# I2C_Expander.net
KiCad netlist of a schematic drawn in Altium Designer
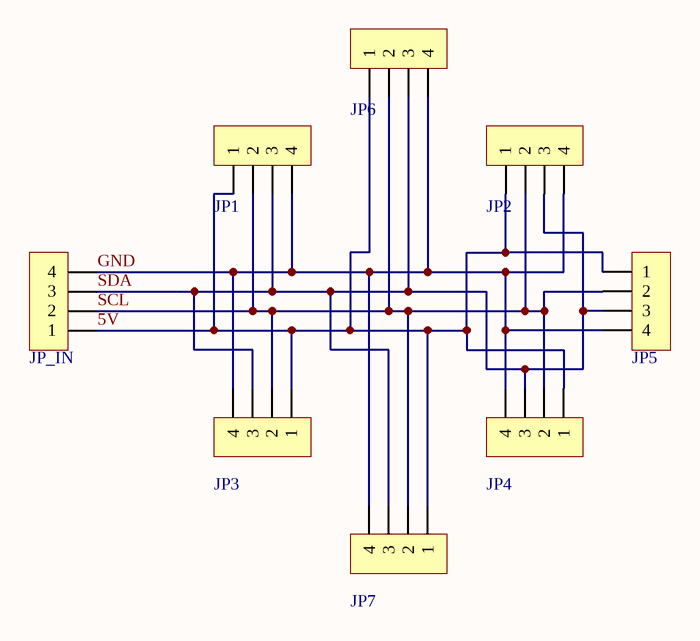
[diagram p0: I2C_Expander.SchDoc]

(export (version "E")
  (design (tool "Eeschema 10.0.6"))
  (components
    (comp (ref "JP1")
      (value "HDR-1X4")
      (footprint "MX 1.25-WS-4P")
      (description "4P接插件")
      (fields (field (name "版权归属") "源创客"))
      (libsource (lib "") (part "Header 4_1"))
    )
    (comp (ref "JP2")
      (value "HDR-1X4")
      (footprint "MX 1.25-WS-4P")
      (description "4P接插件")
      (fields (field (name "版权归属") "源创客"))
      (libsource (lib "") (part "Header 4_1"))
    )
    (comp (ref "JP3")
      (value "HDR-1X4")
      (footprint "MX 1.25-WS-4P")
      (description "4P接插件")
      (fields (field (name "版权归属") "源创客"))
      (libsource (lib "4.2   - 接插件-脚距1.25") (part "Header 4"))
    )
    (comp (ref "JP4")
      (value "HDR-1X4")
      (footprint "MX 1.25-WS-4P")
      (description "4P接插件")
      (fields (field (name "版权归属") "源创客"))
      (libsource (lib "4.2   - 接插件-脚距1.25") (part "Header 4"))
    )
    (comp (ref "JP5")
      (value "HDR-1X4")
      (footprint "HDR2.54-LI-4P")
      (description "4P接插件")
      (fields (field (name "版权归属") "源创客"))
      (libsource (lib "") (part "Header 4_1"))
    )
    (comp (ref "JP6")
      (value "HDR-1X4")
      (footprint "HDR2.54-LI-4P")
      (description "4P接插件")
      (fields (field (name "版权归属") "源创客"))
      (libsource (lib "4.5   - 接插件-脚距2.54") (part "Header 4"))
    )
    (comp (ref "JP7")
      (value "HDR-1X4")
      (footprint "HDR2.54-LI-4P")
      (description "4P接插件")
      (fields (field (name "版权归属") "源创客"))
      (libsource (lib "") (part "Header 4_2"))
    )
    (comp (ref "JP_IN")
      (value "HDR-1X4")
      (footprint "MX 1.25-WS-4P")
      (description "4P接插件")
      (fields (field (name "版权归属") "源创客"))
      (libsource (lib "") (part "Header 4_2"))
    )
  )
  (nets
    (net (code "1") (name "/5V") (class "Default")
      (node (ref "JP1") (pin "1") (pinfunction "1_1") (pintype "passive"))
      (node (ref "JP2") (pin "1") (pinfunction "1_1") (pintype "passive"))
      (node (ref "JP3") (pin "1") (pinfunction "1_1") (pintype "passive"))
      (node (ref "JP4") (pin "1") (pinfunction "1_1") (pintype "passive"))
      (node (ref "JP5") (pin "1") (pinfunction "1_1") (pintype "passive"))
      (node (ref "JP6") (pin "1") (pinfunction "1_1") (pintype "passive"))
      (node (ref "JP7") (pin "1") (pinfunction "1_1") (pintype "passive"))
      (node (ref "JP_IN") (pin "1") (pinfunction "1_1") (pintype "passive"))
    )
    (net (code "2") (name "/GND") (class "Default")
      (node (ref "JP1") (pin "4") (pinfunction "4_4") (pintype "passive"))
      (node (ref "JP2") (pin "4") (pinfunction "4_4") (pintype "passive"))
      (node (ref "JP3") (pin "4") (pinfunction "4_4") (pintype "passive"))
      (node (ref "JP4") (pin "4") (pinfunction "4_4") (pintype "passive"))
      (node (ref "JP5") (pin "4") (pinfunction "4_4") (pintype "passive"))
      (node (ref "JP6") (pin "4") (pinfunction "4_4") (pintype "passive"))
      (node (ref "JP7") (pin "4") (pinfunction "4_4") (pintype "passive"))
      (node (ref "JP_IN") (pin "4") (pinfunction "4_4") (pintype "passive"))
    )
    (net (code "3") (name "/SCL") (class "Default")
      (node (ref "JP1") (pin "2") (pinfunction "2_2") (pintype "passive"))
      (node (ref "JP2") (pin "2") (pinfunction "2_2") (pintype "passive"))
      (node (ref "JP3") (pin "2") (pinfunction "2_2") (pintype "passive"))
      (node (ref "JP4") (pin "2") (pinfunction "2_2") (pintype "passive"))
      (node (ref "JP5") (pin "2") (pinfunction "2_2") (pintype "passive"))
      (node (ref "JP6") (pin "2") (pinfunction "2_2") (pintype "passive"))
      (node (ref "JP7") (pin "2") (pinfunction "2_2") (pintype "passive"))
      (node (ref "JP_IN") (pin "2") (pinfunction "2_2") (pintype "passive"))
    )
    (net (code "4") (name "/SDA") (class "Default")
      (node (ref "JP1") (pin "3") (pinfunction "3_3") (pintype "passive"))
      (node (ref "JP2") (pin "3") (pinfunction "3_3") (pintype "passive"))
      (node (ref "JP3") (pin "3") (pinfunction "3_3") (pintype "passive"))
      (node (ref "JP4") (pin "3") (pinfunction "3_3") (pintype "passive"))
      (node (ref "JP5") (pin "3") (pinfunction "3_3") (pintype "passive"))
      (node (ref "JP6") (pin "3") (pinfunction "3_3") (pintype "passive"))
      (node (ref "JP7") (pin "3") (pinfunction "3_3") (pintype "passive"))
      (node (ref "JP_IN") (pin "3") (pinfunction "3_3") (pintype "passive"))
    )
  )
)
